# Filla_GPS_2015_Rev1.net
KiCad netlist of a schematic drawn in EAGLE
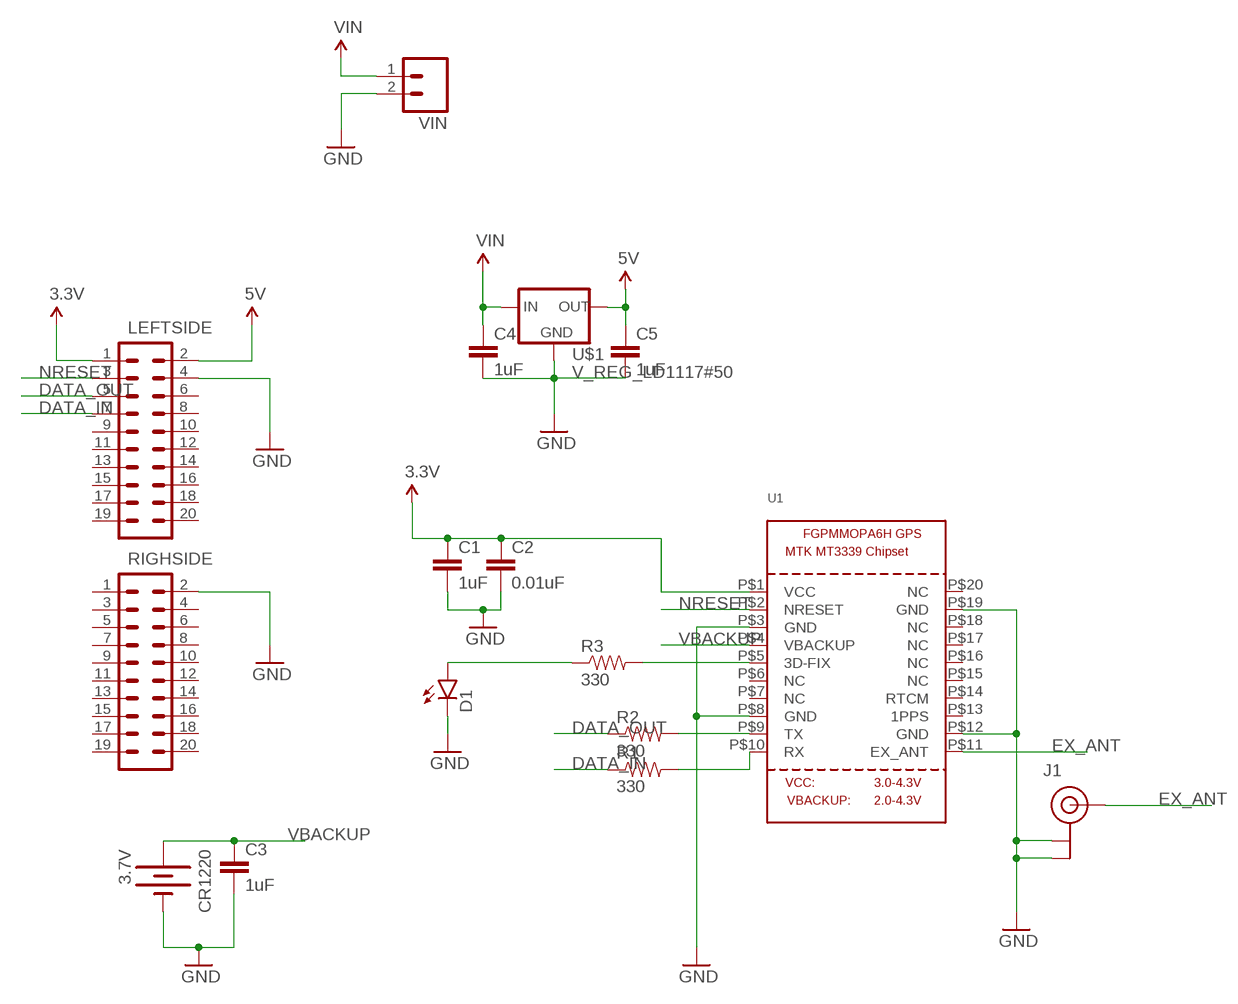
[diagram p0: schematic, sheet 1]

(export (version "E")
  (design (tool "Eeschema 10.0.6"))
  (components
    (comp (ref "C1")
      (value "1uF")
      (footprint "eagle-import:1206")
      (libsource (lib "eagle-import") (part "CAP1206"))
    )
    (comp (ref "C2")
      (value "0.01uF")
      (footprint "eagle-import:1206")
      (libsource (lib "eagle-import") (part "CAP1206"))
    )
    (comp (ref "C3")
      (value "1uF")
      (footprint "eagle-import:1206")
      (libsource (lib "eagle-import") (part "CAP1206"))
    )
    (comp (ref "C4")
      (value "1uF")
      (footprint "eagle-import:1206")
      (libsource (lib "eagle-import") (part "CAP1206"))
    )
    (comp (ref "C5")
      (value "1uF")
      (footprint "eagle-import:1206")
      (libsource (lib "eagle-import") (part "CAP1206"))
    )
    (comp (ref "CR1220")
      (value "3.7V")
      (footprint "eagle-import:BATTCON_12MM")
      (libsource (lib "eagle-import") (part "BATTERY12MM"))
    )
    (comp (ref "D1")
      (value "LED1206")
      (footprint "eagle-import:LED-1206")
      (libsource (lib "eagle-import") (part "LED1206"))
    )
    (comp (ref "J1")
      (value "U.FL")
      (footprint "eagle-import:U.FL")
      (libsource (lib "eagle-import") (part "U.FL"))
    )
    (comp (ref "LEFTSIDE")
      (value "M10X2")
      (footprint "eagle-import:2X10")
      (libsource (lib "eagle-import") (part "M10X2"))
    )
    (comp (ref "R1")
      (value "330")
      (footprint "eagle-import:1206")
      (libsource (lib "eagle-import") (part "RESISTOR1206"))
    )
    (comp (ref "R2")
      (value "330")
      (footprint "eagle-import:1206")
      (libsource (lib "eagle-import") (part "RESISTOR1206"))
    )
    (comp (ref "R3")
      (value "330")
      (footprint "eagle-import:1206")
      (libsource (lib "eagle-import") (part "RESISTOR1206"))
    )
    (comp (ref "RIGHSIDE")
      (value "M10X2")
      (footprint "eagle-import:2X10")
      (libsource (lib "eagle-import") (part "M10X2"))
    )
    (comp (ref "U$1")
      (value "V_REG_LD1117#50")
      (footprint "eagle-import:SOT223")
      (libsource (lib "eagle-import") (part "V_REG_MIC2920"))
    )
    (comp (ref "U1")
      (value "GPS_FGPMMOPA6H")
      (footprint "eagle-import:FGPMMOPA6H")
      (libsource (lib "eagle-import") (part "GPS_FGPMMOPA6H"))
    )
    (comp (ref "VIN")
      (value "M02PTH")
      (footprint "eagle-import:1X02")
      (libsource (lib "eagle-import") (part "M02PTH"))
    )
  )
  (nets
    (net (code "1") (name "/DATA_IN") (class "Default")
      (node (ref "LEFTSIDE") (pin "7") (pinfunction "7_7") (pintype "passive"))
      (node (ref "R1") (pin "1") (pinfunction "1_1") (pintype "passive"))
    )
    (net (code "2") (name "/DATA_OUT") (class "Default")
      (node (ref "LEFTSIDE") (pin "5") (pinfunction "5_5") (pintype "passive"))
      (node (ref "R2") (pin "1") (pinfunction "1_1") (pintype "passive"))
    )
    (net (code "3") (name "/EX_ANT") (class "Default")
      (node (ref "J1") (pin "P$3") (pinfunction "SIGNAL_P$3") (pintype "bidirectional"))
      (node (ref "U1") (pin "P$11") (pinfunction "EX_ANT_P$11") (pintype "bidirectional"))
    )
    (net (code "4") (name "/NRESET") (class "Default")
      (node (ref "LEFTSIDE") (pin "3") (pinfunction "3_3") (pintype "passive"))
      (node (ref "U1") (pin "P$2") (pinfunction "NRESET_P$2") (pintype "bidirectional"))
    )
    (net (code "5") (name "/VBACKUP") (class "Default")
      (node (ref "C3") (pin "1") (pinfunction "1_1") (pintype "passive"))
      (node (ref "CR1220") (pin "PWR@1") (pinfunction "+_PWR@1") (pintype "power_in"))
      (node (ref "U1") (pin "P$4") (pinfunction "VBACKUP_P$4") (pintype "bidirectional"))
    )
    (net (code "6") (name "3.3V") (class "Default")
      (node (ref "C1") (pin "1") (pinfunction "1_1") (pintype "passive"))
      (node (ref "C2") (pin "1") (pinfunction "1_1") (pintype "passive"))
      (node (ref "LEFTSIDE") (pin "1") (pinfunction "1_1") (pintype "passive"))
      (node (ref "U1") (pin "P$1") (pinfunction "VCC_P$1") (pintype "bidirectional"))
    )
    (net (code "7") (name "5V") (class "Default")
      (node (ref "C5") (pin "1") (pinfunction "1_1") (pintype "passive"))
      (node (ref "LEFTSIDE") (pin "2") (pinfunction "2_2") (pintype "passive"))
      (node (ref "U$1") (pin "3") (pinfunction "OUT_3") (pintype "output"))
    )
    (net (code "8") (name "GND") (class "Default")
      (node (ref "C1") (pin "2") (pinfunction "2_2") (pintype "passive"))
      (node (ref "C2") (pin "2") (pinfunction "2_2") (pintype "passive"))
      (node (ref "C3") (pin "2") (pinfunction "2_2") (pintype "passive"))
      (node (ref "C4") (pin "2") (pinfunction "2_2") (pintype "passive"))
      (node (ref "C5") (pin "2") (pinfunction "2_2") (pintype "passive"))
      (node (ref "CR1220") (pin "GND") (pinfunction "-_GND") (pintype "power_in"))
      (node (ref "D1") (pin "C") (pinfunction "C_C") (pintype "passive"))
      (node (ref "J1") (pin "P$1") (pinfunction "GND_P$1") (pintype "bidirectional"))
      (node (ref "J1") (pin "P$2") (pinfunction "GND_P$2") (pintype "bidirectional"))
      (node (ref "LEFTSIDE") (pin "4") (pinfunction "4_4") (pintype "passive"))
      (node (ref "RIGHSIDE") (pin "2") (pinfunction "2_2") (pintype "passive"))
      (node (ref "U$1") (pin "2") (pinfunction "GND_2") (pintype "input"))
      (node (ref "U1") (pin "P$12") (pinfunction "GND_P$12") (pintype "bidirectional"))
      (node (ref "U1") (pin "P$19") (pinfunction "GND_P$19") (pintype "bidirectional"))
      (node (ref "U1") (pin "P$3") (pinfunction "GND_P$3") (pintype "bidirectional"))
      (node (ref "U1") (pin "P$8") (pinfunction "GND_P$8") (pintype "bidirectional"))
      (node (ref "VIN") (pin "2") (pinfunction "2_2") (pintype "passive"))
    )
    (net (code "9") (name "Net-(D1-PadA)") (class "Default")
      (node (ref "D1") (pin "A") (pinfunction "A_A") (pintype "passive"))
      (node (ref "R3") (pin "1") (pinfunction "1_1") (pintype "passive"))
    )
    (net (code "10") (name "Net-(U1-3D-FIX)") (class "Default")
      (node (ref "R3") (pin "2") (pinfunction "2_2") (pintype "passive"))
      (node (ref "U1") (pin "P$5") (pinfunction "3D-FIX_P$5") (pintype "bidirectional"))
    )
    (net (code "11") (name "Net-(U1-RX)") (class "Default")
      (node (ref "R1") (pin "2") (pinfunction "2_2") (pintype "passive"))
      (node (ref "U1") (pin "P$10") (pinfunction "RX_P$10") (pintype "bidirectional"))
    )
    (net (code "12") (name "Net-(U1-TX)") (class "Default")
      (node (ref "R2") (pin "2") (pinfunction "2_2") (pintype "passive"))
      (node (ref "U1") (pin "P$9") (pinfunction "TX_P$9") (pintype "bidirectional"))
    )
    (net (code "13") (name "VIN") (class "Default")
      (node (ref "C4") (pin "1") (pinfunction "1_1") (pintype "passive"))
      (node (ref "U$1") (pin "1") (pinfunction "IN_1") (pintype "input"))
      (node (ref "VIN") (pin "1") (pinfunction "1_1") (pintype "passive"))
    )
    (net (code "14") (name "unconnected-(LEFTSIDE-Pad6)") (class "Default")
      (node (ref "LEFTSIDE") (pin "6") (pinfunction "6_6") (pintype "passive"))
    )
    (net (code "15") (name "unconnected-(LEFTSIDE-Pad8)") (class "Default")
      (node (ref "LEFTSIDE") (pin "8") (pinfunction "8_8") (pintype "passive"))
    )
    (net (code "16") (name "unconnected-(LEFTSIDE-Pad9)") (class "Default")
      (node (ref "LEFTSIDE") (pin "9") (pinfunction "9_9") (pintype "passive"))
    )
    (net (code "17") (name "unconnected-(LEFTSIDE-Pad10)") (class "Default")
      (node (ref "LEFTSIDE") (pin "10") (pinfunction "10_10") (pintype "passive"))
    )
    (net (code "18") (name "unconnected-(LEFTSIDE-Pad11)") (class "Default")
      (node (ref "LEFTSIDE") (pin "11") (pinfunction "11_11") (pintype "passive"))
    )
    (net (code "19") (name "unconnected-(LEFTSIDE-Pad12)") (class "Default")
      (node (ref "LEFTSIDE") (pin "12") (pinfunction "12_12") (pintype "passive"))
    )
    (net (code "20") (name "unconnected-(LEFTSIDE-Pad13)") (class "Default")
      (node (ref "LEFTSIDE") (pin "13") (pinfunction "13_13") (pintype "passive"))
    )
    (net (code "21") (name "unconnected-(LEFTSIDE-Pad14)") (class "Default")
      (node (ref "LEFTSIDE") (pin "14") (pinfunction "14_14") (pintype "passive"))
    )
    (net (code "22") (name "unconnected-(LEFTSIDE-Pad15)") (class "Default")
      (node (ref "LEFTSIDE") (pin "15") (pinfunction "15_15") (pintype "passive"))
    )
    (net (code "23") (name "unconnected-(LEFTSIDE-Pad16)") (class "Default")
      (node (ref "LEFTSIDE") (pin "16") (pinfunction "16_16") (pintype "passive"))
    )
    (net (code "24") (name "unconnected-(LEFTSIDE-Pad17)") (class "Default")
      (node (ref "LEFTSIDE") (pin "17") (pinfunction "17_17") (pintype "passive"))
    )
    (net (code "25") (name "unconnected-(LEFTSIDE-Pad18)") (class "Default")
      (node (ref "LEFTSIDE") (pin "18") (pinfunction "18_18") (pintype "passive"))
    )
    (net (code "26") (name "unconnected-(LEFTSIDE-Pad19)") (class "Default")
      (node (ref "LEFTSIDE") (pin "19") (pinfunction "19_19") (pintype "passive"))
    )
    (net (code "27") (name "unconnected-(LEFTSIDE-Pad20)") (class "Default")
      (node (ref "LEFTSIDE") (pin "20") (pinfunction "20_20") (pintype "passive"))
    )
    (net (code "28") (name "unconnected-(RIGHSIDE-Pad1)") (class "Default")
      (node (ref "RIGHSIDE") (pin "1") (pinfunction "1_1") (pintype "passive"))
    )
    (net (code "29") (name "unconnected-(RIGHSIDE-Pad3)") (class "Default")
      (node (ref "RIGHSIDE") (pin "3") (pinfunction "3_3") (pintype "passive"))
    )
    (net (code "30") (name "unconnected-(RIGHSIDE-Pad4)") (class "Default")
      (node (ref "RIGHSIDE") (pin "4") (pinfunction "4_4") (pintype "passive"))
    )
    (net (code "31") (name "unconnected-(RIGHSIDE-Pad5)") (class "Default")
      (node (ref "RIGHSIDE") (pin "5") (pinfunction "5_5") (pintype "passive"))
    )
    (net (code "32") (name "unconnected-(RIGHSIDE-Pad6)") (class "Default")
      (node (ref "RIGHSIDE") (pin "6") (pinfunction "6_6") (pintype "passive"))
    )
    (net (code "33") (name "unconnected-(RIGHSIDE-Pad7)") (class "Default")
      (node (ref "RIGHSIDE") (pin "7") (pinfunction "7_7") (pintype "passive"))
    )
    (net (code "34") (name "unconnected-(RIGHSIDE-Pad8)") (class "Default")
      (node (ref "RIGHSIDE") (pin "8") (pinfunction "8_8") (pintype "passive"))
    )
    (net (code "35") (name "unconnected-(RIGHSIDE-Pad9)") (class "Default")
      (node (ref "RIGHSIDE") (pin "9") (pinfunction "9_9") (pintype "passive"))
    )
    (net (code "36") (name "unconnected-(RIGHSIDE-Pad10)") (class "Default")
      (node (ref "RIGHSIDE") (pin "10") (pinfunction "10_10") (pintype "passive"))
    )
    (net (code "37") (name "unconnected-(RIGHSIDE-Pad11)") (class "Default")
      (node (ref "RIGHSIDE") (pin "11") (pinfunction "11_11") (pintype "passive"))
    )
    (net (code "38") (name "unconnected-(RIGHSIDE-Pad12)") (class "Default")
      (node (ref "RIGHSIDE") (pin "12") (pinfunction "12_12") (pintype "passive"))
    )
    (net (code "39") (name "unconnected-(RIGHSIDE-Pad13)") (class "Default")
      (node (ref "RIGHSIDE") (pin "13") (pinfunction "13_13") (pintype "passive"))
    )
    (net (code "40") (name "unconnected-(RIGHSIDE-Pad14)") (class "Default")
      (node (ref "RIGHSIDE") (pin "14") (pinfunction "14_14") (pintype "passive"))
    )
    (net (code "41") (name "unconnected-(RIGHSIDE-Pad15)") (class "Default")
      (node (ref "RIGHSIDE") (pin "15") (pinfunction "15_15") (pintype "passive"))
    )
    (net (code "42") (name "unconnected-(RIGHSIDE-Pad16)") (class "Default")
      (node (ref "RIGHSIDE") (pin "16") (pinfunction "16_16") (pintype "passive"))
    )
    (net (code "43") (name "unconnected-(RIGHSIDE-Pad17)") (class "Default")
      (node (ref "RIGHSIDE") (pin "17") (pinfunction "17_17") (pintype "passive"))
    )
    (net (code "44") (name "unconnected-(RIGHSIDE-Pad18)") (class "Default")
      (node (ref "RIGHSIDE") (pin "18") (pinfunction "18_18") (pintype "passive"))
    )
    (net (code "45") (name "unconnected-(RIGHSIDE-Pad19)") (class "Default")
      (node (ref "RIGHSIDE") (pin "19") (pinfunction "19_19") (pintype "passive"))
    )
    (net (code "46") (name "unconnected-(RIGHSIDE-Pad20)") (class "Default")
      (node (ref "RIGHSIDE") (pin "20") (pinfunction "20_20") (pintype "passive"))
    )
    (net (code "47") (name "unconnected-(U1-1PPS-PadP$13)") (class "Default")
      (node (ref "U1") (pin "P$13") (pinfunction "1PPS_P$13") (pintype "bidirectional"))
    )
    (net (code "48") (name "unconnected-(U1-NC-PadP$6)") (class "Default")
      (node (ref "U1") (pin "P$6") (pinfunction "NC_P$6") (pintype "bidirectional"))
    )
    (net (code "49") (name "unconnected-(U1-NC-PadP$7)") (class "Default")
      (node (ref "U1") (pin "P$7") (pinfunction "NC_P$7") (pintype "bidirectional"))
    )
    (net (code "50") (name "unconnected-(U1-NC-PadP$15)") (class "Default")
      (node (ref "U1") (pin "P$15") (pinfunction "NC_P$15") (pintype "bidirectional"))
    )
    (net (code "51") (name "unconnected-(U1-NC-PadP$16)") (class "Default")
      (node (ref "U1") (pin "P$16") (pinfunction "NC_P$16") (pintype "bidirectional"))
    )
    (net (code "52") (name "unconnected-(U1-NC-PadP$17)") (class "Default")
      (node (ref "U1") (pin "P$17") (pinfunction "NC_P$17") (pintype "bidirectional"))
    )
    (net (code "53") (name "unconnected-(U1-NC-PadP$18)") (class "Default")
      (node (ref "U1") (pin "P$18") (pinfunction "NC_P$18") (pintype "bidirectional"))
    )
    (net (code "54") (name "unconnected-(U1-NC-PadP$20)") (class "Default")
      (node (ref "U1") (pin "P$20") (pinfunction "NC_P$20") (pintype "bidirectional"))
    )
    (net (code "55") (name "unconnected-(U1-RTCM-PadP$14)") (class "Default")
      (node (ref "U1") (pin "P$14") (pinfunction "RTCM_P$14") (pintype "bidirectional"))
    )
  )
)
